# Lab3-4.net
KiCad netlist of a schematic drawn in Altium Designer
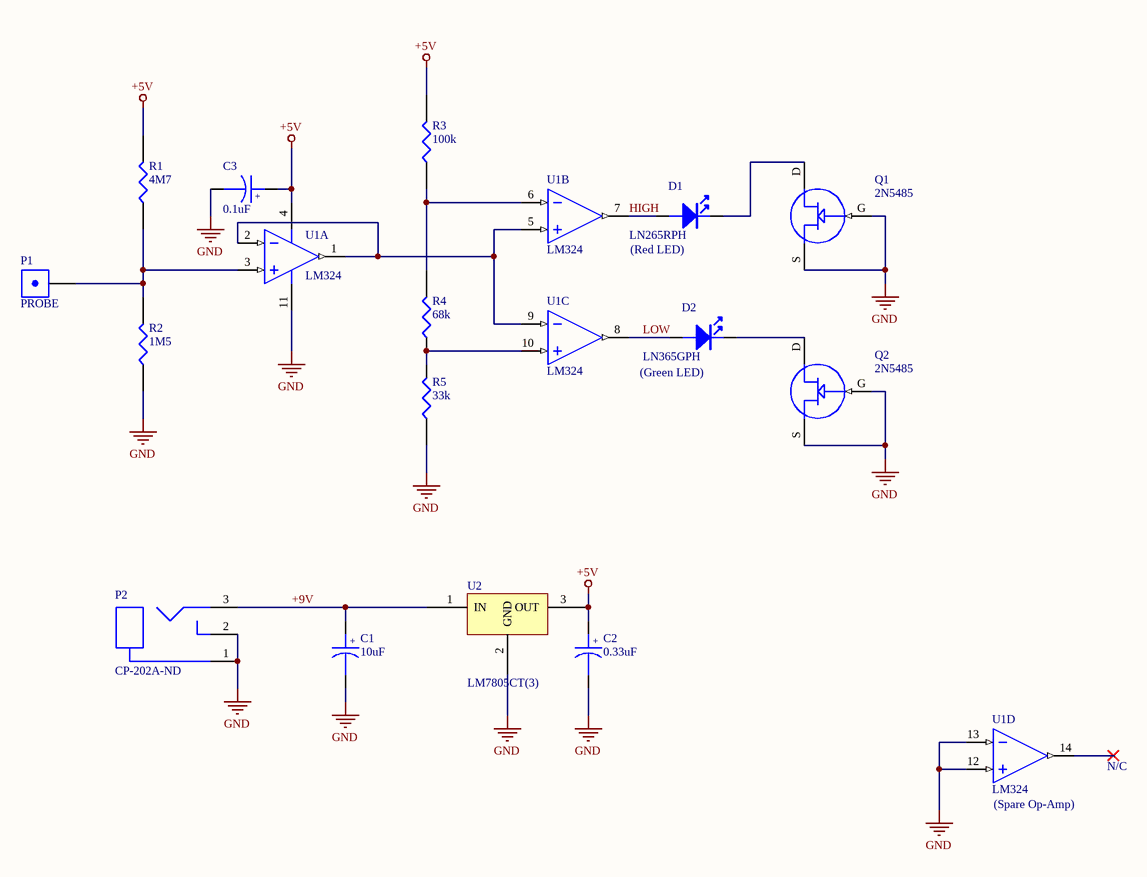
[diagram p0: Lab3-4.SchDoc]

(export (version "E")
  (design (tool "Eeschema 10.0.6"))
  (components
    (comp (ref "C1")
      (value "10uF")
      (footprint "RAD0.2-POL")
      (description "Polarized Capacitor")
      (libsource (lib "ECET231SCHLIB_Rev01") (part "CAPACITOR POL"))
    )
    (comp (ref "C2")
      (value "0.33uF")
      (footprint "RAD0.2")
      (description "Polarized Capacitor")
      (libsource (lib "ECET231SCHLIB_Rev01") (part "CAPACITOR POL"))
    )
    (comp (ref "C3")
      (value "0.1uF")
      (footprint "RAD0.2")
      (description "Polarized Capacitor")
      (libsource (lib "ECET231SCHLIB_Rev01") (part "CAPACITOR POL"))
    )
    (comp (ref "D1")
      (value "LN265RPH")
      (footprint "LN265PH")
      (description "Light Emitting Diode LED")
      (libsource (lib "ECET231SCHLIB_Rev01") (part "LED"))
    )
    (comp (ref "D2")
      (value "LN365GPH")
      (footprint "LN265PH")
      (description "Light Emitting Diode LED")
      (libsource (lib "ECET231SCHLIB_Rev01") (part "LED"))
    )
    (comp (ref "P1")
      (value "PROBE")
      (footprint "PROBE")
      (description "Probe")
      (libsource (lib "ECET231SCHLIB_Rev01") (part "PROBE"))
    )
    (comp (ref "P2")
      (value "CP-202A-ND")
      (footprint "CP-202A-ND")
      (description "Male Power Jack, PCB")
      (libsource (lib "ECET231SCHLIB_Rev01") (part "CP-202A-ND"))
    )
    (comp (ref "Q1")
      (value "2N5485")
      (description "N-channel JFET")
      (libsource (lib "ECET231SCHLIB_Rev01") (part "2N5485"))
    )
    (comp (ref "Q2")
      (value "2N5485")
      (footprint "TO-92A")
      (description "N-channel JFET")
      (libsource (lib "ECET231SCHLIB_Rev01") (part "2N5485"))
    )
    (comp (ref "R1")
      (value "4M7")
      (footprint "Axial0.5")
      (description "Resistor")
      (libsource (lib "ECET231SCHLIB_Rev01") (part "RES1"))
    )
    (comp (ref "R2")
      (value "1M5")
      (footprint "Axial0.5")
      (description "Resistor")
      (libsource (lib "ECET231SCHLIB_Rev01") (part "RES1"))
    )
    (comp (ref "R3")
      (value "100k")
      (footprint "Axial0.5")
      (description "Resistor")
      (libsource (lib "ECET231SCHLIB_Rev01") (part "RES1"))
    )
    (comp (ref "R4")
      (value "68k")
      (footprint "Axial0.5")
      (description "Resistor")
      (libsource (lib "ECET231SCHLIB_Rev01") (part "RES1"))
    )
    (comp (ref "R5")
      (value "33k")
      (footprint "Axial0.5")
      (description "Resistor")
      (libsource (lib "ECET231SCHLIB_Rev01") (part "RES1"))
    )
    (comp (ref "U1")
      (value "LM324")
      (footprint "DIP14")
      (description "Quad (4) Operational Amplifier")
      (libsource (lib "ECET231SCHLIB_Rev01") (part "LM324"))
    )
    (comp (ref "U2")
      (value "LM7805CT(3)")
      (footprint "TO-220")
      (description "Three Terminal Voltage Regulator")
      (libsource (lib "ECET231SCHLIB_Rev01") (part "LM7805CT(3)"))
    )
  )
  (nets
    (net (code "1") (name "+5V") (class "Default")
      (node (ref "C2") (pin "1") (pinfunction "1_1") (pintype "passive"))
      (node (ref "C3") (pin "1") (pinfunction "1_1") (pintype "passive"))
      (node (ref "R1") (pin "2") (pinfunction "2_2") (pintype "passive"))
      (node (ref "R3") (pin "2") (pinfunction "2_2") (pintype "passive"))
      (node (ref "U1") (pin "4") (pinfunction "VCC_4") (pintype "power_in"))
      (node (ref "U2") (pin "3") (pinfunction "OUT_3") (pintype "power_in"))
    )
    (net (code "2") (name "/+9V") (class "Default")
      (node (ref "C1") (pin "1") (pinfunction "1_1") (pintype "passive"))
      (node (ref "P2") (pin "3") (pinfunction "3_3") (pintype "passive"))
      (node (ref "U2") (pin "1") (pinfunction "IN_1") (pintype "power_in"))
    )
    (net (code "3") (name "/HIGH") (class "Default")
      (node (ref "D1") (pin "A") (pinfunction "A_A") (pintype "passive"))
      (node (ref "U1") (pin "7") (pinfunction "2_OUT_7") (pintype "output"))
    )
    (net (code "4") (name "/LOW") (class "Default")
      (node (ref "D2") (pin "A") (pinfunction "A_A") (pintype "passive"))
      (node (ref "U1") (pin "8") (pinfunction "3_OUT_8") (pintype "output"))
    )
    (net (code "5") (name "GND") (class "Default")
      (node (ref "C1") (pin "2") (pinfunction "2_2") (pintype "passive"))
      (node (ref "C2") (pin "2") (pinfunction "2_2") (pintype "passive"))
      (node (ref "C3") (pin "2") (pinfunction "2_2") (pintype "passive"))
      (node (ref "P2") (pin "1") (pinfunction "1_1") (pintype "passive"))
      (node (ref "P2") (pin "2") (pinfunction "2_2") (pintype "passive"))
      (node (ref "Q1") (pin "G") (pinfunction "G_G") (pintype "input"))
      (node (ref "Q1") (pin "S") (pinfunction "S_S") (pintype "passive"))
      (node (ref "Q2") (pin "G") (pinfunction "G_G") (pintype "input"))
      (node (ref "Q2") (pin "S") (pinfunction "S_S") (pintype "passive"))
      (node (ref "R2") (pin "1") (pinfunction "1_1") (pintype "passive"))
      (node (ref "R5") (pin "1") (pinfunction "1_1") (pintype "passive"))
      (node (ref "U1") (pin "11") (pinfunction "VEE_11") (pintype "power_in"))
      (node (ref "U1") (pin "12") (pinfunction "4_IN+_12") (pintype "input"))
      (node (ref "U1") (pin "13") (pinfunction "4_IN-_13") (pintype "input"))
      (node (ref "U2") (pin "2") (pinfunction "GND_2") (pintype "power_in"))
    )
    (net (code "6") (name "Net-(D1-PadK)") (class "Default")
      (node (ref "D1") (pin "K") (pinfunction "K_K") (pintype "passive"))
      (node (ref "Q1") (pin "D") (pinfunction "D_D") (pintype "passive"))
    )
    (net (code "7") (name "Net-(D2-PadK)") (class "Default")
      (node (ref "D2") (pin "K") (pinfunction "K_K") (pintype "passive"))
      (node (ref "Q2") (pin "D") (pinfunction "D_D") (pintype "passive"))
    )
    (net (code "8") (name "Net-(U1A-1_IN+)") (class "Default")
      (node (ref "P1") (pin "1") (pinfunction "1_1") (pintype "passive"))
      (node (ref "R1") (pin "1") (pinfunction "1_1") (pintype "passive"))
      (node (ref "R2") (pin "2") (pinfunction "2_2") (pintype "passive"))
      (node (ref "U1") (pin "3") (pinfunction "1_IN+_3") (pintype "input"))
    )
    (net (code "9") (name "Net-(U1A-1_IN-)") (class "Default")
      (node (ref "U1") (pin "1") (pinfunction "1_OUT_1") (pintype "output"))
      (node (ref "U1") (pin "2") (pinfunction "1_IN-_2") (pintype "input"))
      (node (ref "U1") (pin "5") (pinfunction "2_IN+_5") (pintype "input"))
      (node (ref "U1") (pin "9") (pinfunction "3_IN-_9") (pintype "input"))
    )
    (net (code "10") (name "Net-(U1B-2_IN-)") (class "Default")
      (node (ref "R3") (pin "1") (pinfunction "1_1") (pintype "passive"))
      (node (ref "R4") (pin "2") (pinfunction "2_2") (pintype "passive"))
      (node (ref "U1") (pin "6") (pinfunction "2_IN-_6") (pintype "input"))
    )
    (net (code "11") (name "Net-(U1C-3_IN+)") (class "Default")
      (node (ref "R4") (pin "1") (pinfunction "1_1") (pintype "passive"))
      (node (ref "R5") (pin "2") (pinfunction "2_2") (pintype "passive"))
      (node (ref "U1") (pin "10") (pinfunction "3_IN+_10") (pintype "input"))
    )
    (net (code "12") (name "unconnected-(U1D-4_OUT-Pad14)") (class "Default")
      (node (ref "U1") (pin "14") (pinfunction "4_OUT_14") (pintype "output"))
    )
  )
)
